# ALU_OR.net
KiCad netlist of a schematic drawn in Altium Designer
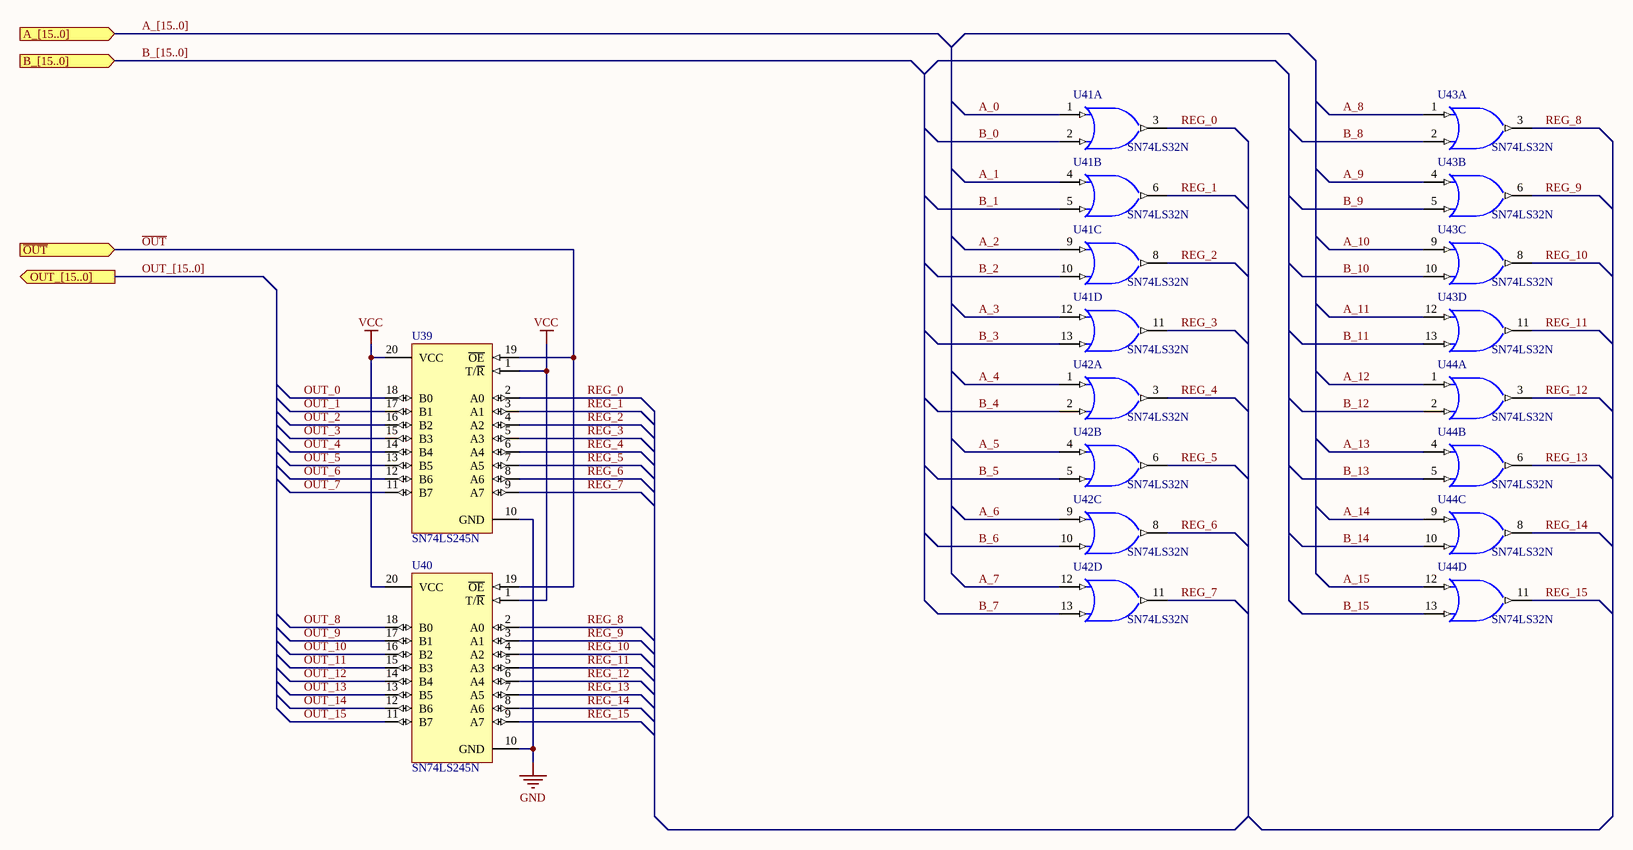
[diagram p0: ALU_OR.SchDoc]

(export (version "E")
  (design (tool "Eeschema 10.0.6"))
  (components
    (comp (ref "U39")
      (value "SN74LS245N")
      (footprint "N020")
      (description "Octal Bus Transceiver with 3-State Outputs")
      (fields (field (name "PUBLISHER") "Altium Limited"))
      (libsource (lib "TI Interface 8-Bit Line Transceiver") (part "SN74LS245N"))
    )
    (comp (ref "U40")
      (value "SN74LS245N")
      (footprint "N020")
      (description "Octal Bus Transceiver with 3-State Outputs")
      (fields (field (name "PUBLISHER") "Altium Limited"))
      (libsource (lib "TI Interface 8-Bit Line Transceiver") (part "SN74LS245N"))
    )
    (comp (ref "U41")
      (value "SN74LS32N")
      (footprint "N014")
      (description "Quadruple 2-Input Positive-OR Gate")
      (fields (field (name "PUBLISHER") "Altium Limited"))
      (libsource (lib "TI Logic Gate 2") (part "SN74LS32N"))
    )
    (comp (ref "U42")
      (value "SN74LS32N")
      (footprint "N014")
      (description "Quadruple 2-Input Positive-OR Gate")
      (fields (field (name "PUBLISHER") "Altium Limited"))
      (libsource (lib "TI Logic Gate 2") (part "SN74LS32N"))
    )
    (comp (ref "U43")
      (value "SN74LS32N")
      (footprint "N014")
      (description "Quadruple 2-Input Positive-OR Gate")
      (fields (field (name "PUBLISHER") "Altium Limited"))
      (libsource (lib "TI Logic Gate 2") (part "SN74LS32N"))
    )
    (comp (ref "U44")
      (value "SN74LS32N")
      (footprint "N014")
      (description "Quadruple 2-Input Positive-OR Gate")
      (fields (field (name "PUBLISHER") "Altium Limited"))
      (libsource (lib "TI Logic Gate 2") (part "SN74LS32N"))
    )
  )
  (nets
    (net (code "1") (name "/A_0") (class "Default")
      (node (ref "U41") (pin "1") (pinfunction "A_1") (pintype "input"))
    )
    (net (code "2") (name "/A_1") (class "Default")
      (node (ref "U41") (pin "4") (pinfunction "A_4") (pintype "input"))
    )
    (net (code "3") (name "/A_2") (class "Default")
      (node (ref "U41") (pin "9") (pinfunction "A_9") (pintype "input"))
    )
    (net (code "4") (name "/A_3") (class "Default")
      (node (ref "U41") (pin "12") (pinfunction "A_12") (pintype "input"))
    )
    (net (code "5") (name "/A_4") (class "Default")
      (node (ref "U42") (pin "1") (pinfunction "A_1") (pintype "input"))
    )
    (net (code "6") (name "/A_5") (class "Default")
      (node (ref "U42") (pin "4") (pinfunction "A_4") (pintype "input"))
    )
    (net (code "7") (name "/A_6") (class "Default")
      (node (ref "U42") (pin "9") (pinfunction "A_9") (pintype "input"))
    )
    (net (code "8") (name "/A_7") (class "Default")
      (node (ref "U42") (pin "12") (pinfunction "A_12") (pintype "input"))
    )
    (net (code "9") (name "/A_8") (class "Default")
      (node (ref "U43") (pin "1") (pinfunction "A_1") (pintype "input"))
    )
    (net (code "10") (name "/A_9") (class "Default")
      (node (ref "U43") (pin "4") (pinfunction "A_4") (pintype "input"))
    )
    (net (code "11") (name "/A_10") (class "Default")
      (node (ref "U43") (pin "9") (pinfunction "A_9") (pintype "input"))
    )
    (net (code "12") (name "/A_11") (class "Default")
      (node (ref "U43") (pin "12") (pinfunction "A_12") (pintype "input"))
    )
    (net (code "13") (name "/A_12") (class "Default")
      (node (ref "U44") (pin "1") (pinfunction "A_1") (pintype "input"))
    )
    (net (code "14") (name "/A_13") (class "Default")
      (node (ref "U44") (pin "4") (pinfunction "A_4") (pintype "input"))
    )
    (net (code "15") (name "/A_14") (class "Default")
      (node (ref "U44") (pin "9") (pinfunction "A_9") (pintype "input"))
    )
    (net (code "16") (name "/A_15") (class "Default")
      (node (ref "U44") (pin "12") (pinfunction "A_12") (pintype "input"))
    )
    (net (code "18") (name "/B_0") (class "Default")
      (node (ref "U41") (pin "2") (pinfunction "B_2") (pintype "input"))
    )
    (net (code "19") (name "/B_1") (class "Default")
      (node (ref "U41") (pin "5") (pinfunction "B_5") (pintype "input"))
    )
    (net (code "20") (name "/B_2") (class "Default")
      (node (ref "U41") (pin "10") (pinfunction "B_10") (pintype "input"))
    )
    (net (code "21") (name "/B_3") (class "Default")
      (node (ref "U41") (pin "13") (pinfunction "B_13") (pintype "input"))
    )
    (net (code "22") (name "/B_4") (class "Default")
      (node (ref "U42") (pin "2") (pinfunction "B_2") (pintype "input"))
    )
    (net (code "23") (name "/B_5") (class "Default")
      (node (ref "U42") (pin "5") (pinfunction "B_5") (pintype "input"))
    )
    (net (code "24") (name "/B_6") (class "Default")
      (node (ref "U42") (pin "10") (pinfunction "B_10") (pintype "input"))
    )
    (net (code "25") (name "/B_7") (class "Default")
      (node (ref "U42") (pin "13") (pinfunction "B_13") (pintype "input"))
    )
    (net (code "26") (name "/B_8") (class "Default")
      (node (ref "U43") (pin "2") (pinfunction "B_2") (pintype "input"))
    )
    (net (code "27") (name "/B_9") (class "Default")
      (node (ref "U43") (pin "5") (pinfunction "B_5") (pintype "input"))
    )
    (net (code "28") (name "/B_10") (class "Default")
      (node (ref "U43") (pin "10") (pinfunction "B_10") (pintype "input"))
    )
    (net (code "29") (name "/B_11") (class "Default")
      (node (ref "U43") (pin "13") (pinfunction "B_13") (pintype "input"))
    )
    (net (code "30") (name "/B_12") (class "Default")
      (node (ref "U44") (pin "2") (pinfunction "B_2") (pintype "input"))
    )
    (net (code "31") (name "/B_13") (class "Default")
      (node (ref "U44") (pin "5") (pinfunction "B_5") (pintype "input"))
    )
    (net (code "32") (name "/B_14") (class "Default")
      (node (ref "U44") (pin "10") (pinfunction "B_10") (pintype "input"))
    )
    (net (code "33") (name "/B_15") (class "Default")
      (node (ref "U44") (pin "13") (pinfunction "B_13") (pintype "input"))
    )
    (net (code "35") (name "/OUT_0") (class "Default")
      (node (ref "U39") (pin "18") (pinfunction "B0_18") (pintype "bidirectional"))
    )
    (net (code "36") (name "/OUT_1") (class "Default")
      (node (ref "U39") (pin "17") (pinfunction "B1_17") (pintype "bidirectional"))
    )
    (net (code "37") (name "/OUT_2") (class "Default")
      (node (ref "U39") (pin "16") (pinfunction "B2_16") (pintype "bidirectional"))
    )
    (net (code "38") (name "/OUT_3") (class "Default")
      (node (ref "U39") (pin "15") (pinfunction "B3_15") (pintype "bidirectional"))
    )
    (net (code "39") (name "/OUT_4") (class "Default")
      (node (ref "U39") (pin "14") (pinfunction "B4_14") (pintype "bidirectional"))
    )
    (net (code "40") (name "/OUT_5") (class "Default")
      (node (ref "U39") (pin "13") (pinfunction "B5_13") (pintype "bidirectional"))
    )
    (net (code "41") (name "/OUT_6") (class "Default")
      (node (ref "U39") (pin "12") (pinfunction "B6_12") (pintype "bidirectional"))
    )
    (net (code "42") (name "/OUT_7") (class "Default")
      (node (ref "U39") (pin "11") (pinfunction "B7_11") (pintype "bidirectional"))
    )
    (net (code "43") (name "/OUT_8") (class "Default")
      (node (ref "U40") (pin "18") (pinfunction "B0_18") (pintype "bidirectional"))
    )
    (net (code "44") (name "/OUT_9") (class "Default")
      (node (ref "U40") (pin "17") (pinfunction "B1_17") (pintype "bidirectional"))
    )
    (net (code "45") (name "/OUT_10") (class "Default")
      (node (ref "U40") (pin "16") (pinfunction "B2_16") (pintype "bidirectional"))
    )
    (net (code "46") (name "/OUT_11") (class "Default")
      (node (ref "U40") (pin "15") (pinfunction "B3_15") (pintype "bidirectional"))
    )
    (net (code "47") (name "/OUT_12") (class "Default")
      (node (ref "U40") (pin "14") (pinfunction "B4_14") (pintype "bidirectional"))
    )
    (net (code "48") (name "/OUT_13") (class "Default")
      (node (ref "U40") (pin "13") (pinfunction "B5_13") (pintype "bidirectional"))
    )
    (net (code "49") (name "/OUT_14") (class "Default")
      (node (ref "U40") (pin "12") (pinfunction "B6_12") (pintype "bidirectional"))
    )
    (net (code "50") (name "/OUT_15") (class "Default")
      (node (ref "U40") (pin "11") (pinfunction "B7_11") (pintype "bidirectional"))
    )
    (net (code "52") (name "/REG_0") (class "Default")
      (node (ref "U39") (pin "2") (pinfunction "A0_2") (pintype "bidirectional"))
      (node (ref "U41") (pin "3") (pinfunction "Y_3") (pintype "output"))
    )
    (net (code "53") (name "/REG_1") (class "Default")
      (node (ref "U39") (pin "3") (pinfunction "A1_3") (pintype "bidirectional"))
      (node (ref "U41") (pin "6") (pinfunction "Y_6") (pintype "output"))
    )
    (net (code "54") (name "/REG_2") (class "Default")
      (node (ref "U39") (pin "4") (pinfunction "A2_4") (pintype "bidirectional"))
      (node (ref "U41") (pin "8") (pinfunction "Y_8") (pintype "output"))
    )
    (net (code "55") (name "/REG_3") (class "Default")
      (node (ref "U39") (pin "5") (pinfunction "A3_5") (pintype "bidirectional"))
      (node (ref "U41") (pin "11") (pinfunction "Y_11") (pintype "output"))
    )
    (net (code "56") (name "/REG_4") (class "Default")
      (node (ref "U39") (pin "6") (pinfunction "A4_6") (pintype "bidirectional"))
      (node (ref "U42") (pin "3") (pinfunction "Y_3") (pintype "output"))
    )
    (net (code "57") (name "/REG_5") (class "Default")
      (node (ref "U39") (pin "7") (pinfunction "A5_7") (pintype "bidirectional"))
      (node (ref "U42") (pin "6") (pinfunction "Y_6") (pintype "output"))
    )
    (net (code "58") (name "/REG_6") (class "Default")
      (node (ref "U39") (pin "8") (pinfunction "A6_8") (pintype "bidirectional"))
      (node (ref "U42") (pin "8") (pinfunction "Y_8") (pintype "output"))
    )
    (net (code "59") (name "/REG_7") (class "Default")
      (node (ref "U39") (pin "9") (pinfunction "A7_9") (pintype "bidirectional"))
      (node (ref "U42") (pin "11") (pinfunction "Y_11") (pintype "output"))
    )
    (net (code "60") (name "/REG_8") (class "Default")
      (node (ref "U40") (pin "2") (pinfunction "A0_2") (pintype "bidirectional"))
      (node (ref "U43") (pin "3") (pinfunction "Y_3") (pintype "output"))
    )
    (net (code "61") (name "/REG_9") (class "Default")
      (node (ref "U40") (pin "3") (pinfunction "A1_3") (pintype "bidirectional"))
      (node (ref "U43") (pin "6") (pinfunction "Y_6") (pintype "output"))
    )
    (net (code "62") (name "/REG_10") (class "Default")
      (node (ref "U40") (pin "4") (pinfunction "A2_4") (pintype "bidirectional"))
      (node (ref "U43") (pin "8") (pinfunction "Y_8") (pintype "output"))
    )
    (net (code "63") (name "/REG_11") (class "Default")
      (node (ref "U40") (pin "5") (pinfunction "A3_5") (pintype "bidirectional"))
      (node (ref "U43") (pin "11") (pinfunction "Y_11") (pintype "output"))
    )
    (net (code "64") (name "/REG_12") (class "Default")
      (node (ref "U40") (pin "6") (pinfunction "A4_6") (pintype "bidirectional"))
      (node (ref "U44") (pin "3") (pinfunction "Y_3") (pintype "output"))
    )
    (net (code "65") (name "/REG_13") (class "Default")
      (node (ref "U40") (pin "7") (pinfunction "A5_7") (pintype "bidirectional"))
      (node (ref "U44") (pin "6") (pinfunction "Y_6") (pintype "output"))
    )
    (net (code "66") (name "/REG_14") (class "Default")
      (node (ref "U40") (pin "8") (pinfunction "A6_8") (pintype "bidirectional"))
      (node (ref "U44") (pin "8") (pinfunction "Y_8") (pintype "output"))
    )
    (net (code "67") (name "/REG_15") (class "Default")
      (node (ref "U40") (pin "9") (pinfunction "A7_9") (pintype "bidirectional"))
      (node (ref "U44") (pin "11") (pinfunction "Y_11") (pintype "output"))
    )
    (net (code "68") (name "/~{OUT}") (class "Default")
      (node (ref "U39") (pin "19") (pinfunction "~{OE}_19") (pintype "input"))
      (node (ref "U40") (pin "19") (pinfunction "~{OE}_19") (pintype "input"))
    )
    (net (code "69") (name "GND") (class "Default")
      (node (ref "U39") (pin "10") (pinfunction "GND_10") (pintype "power_in"))
      (node (ref "U40") (pin "10") (pinfunction "GND_10") (pintype "power_in"))
      (node (ref "U41") (pin "7") (pinfunction "GND_7") (pintype "power_in"))
      (node (ref "U42") (pin "7") (pinfunction "GND_7") (pintype "power_in"))
      (node (ref "U43") (pin "7") (pinfunction "GND_7") (pintype "power_in"))
      (node (ref "U44") (pin "7") (pinfunction "GND_7") (pintype "power_in"))
    )
    (net (code "70") (name "VCC") (class "Default")
      (node (ref "U39") (pin "1") (pinfunction "T/~{R}_1") (pintype "input"))
      (node (ref "U39") (pin "20") (pinfunction "VCC_20") (pintype "power_in"))
      (node (ref "U40") (pin "1") (pinfunction "T/~{R}_1") (pintype "input"))
      (node (ref "U40") (pin "20") (pinfunction "VCC_20") (pintype "power_in"))
      (node (ref "U41") (pin "14") (pinfunction "VCC_14") (pintype "power_in"))
      (node (ref "U42") (pin "14") (pinfunction "VCC_14") (pintype "power_in"))
      (node (ref "U43") (pin "14") (pinfunction "VCC_14") (pintype "power_in"))
      (node (ref "U44") (pin "14") (pinfunction "VCC_14") (pintype "power_in"))
    )
  )
)
